# esp32B-2A.net
KiCad netlist of a schematic drawn in EAGLE
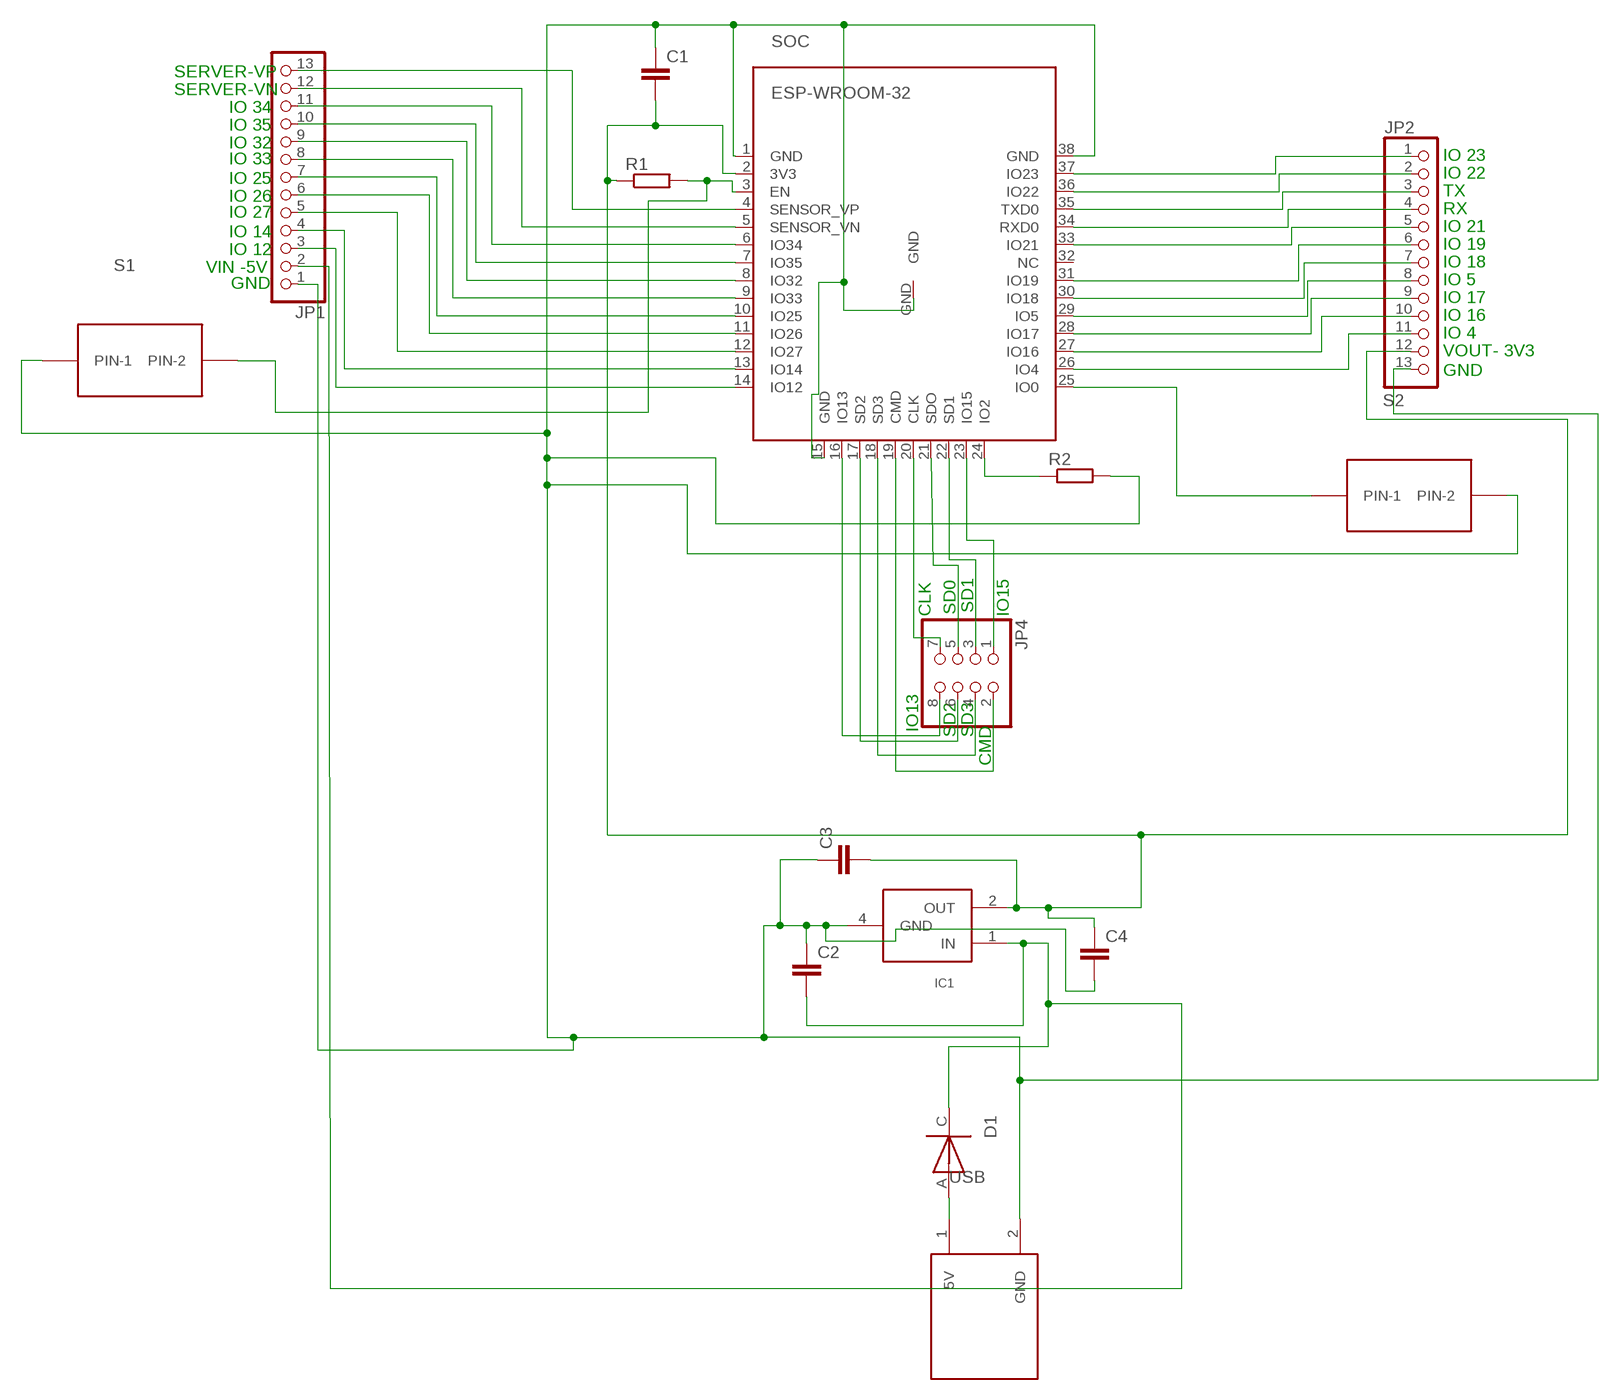
[diagram p0: schematic, sheet 1]

(export (version "E")
  (design (tool "Eeschema 10.0.6"))
  (components
    (comp (ref "C1")
      (value "C-EUC0603")
      (footprint "eagle-import:C0603")
      (libsource (lib "eagle-import") (part "C-EUC0603"))
    )
    (comp (ref "C2")
      (value "C-EUC0603")
      (footprint "eagle-import:C0603")
      (libsource (lib "eagle-import") (part "C-EUC0603"))
    )
    (comp (ref "C3")
      (value "C-EUC1206")
      (footprint "eagle-import:C1206")
      (libsource (lib "eagle-import") (part "C-EUC1206"))
    )
    (comp (ref "C4")
      (value "C-EUC1206")
      (footprint "eagle-import:C1206")
      (libsource (lib "eagle-import") (part "C-EUC1206"))
    )
    (comp (ref "D1")
      (value "DIODE-EX")
      (footprint "eagle-import:SOD80C")
      (libsource (lib "eagle-import") (part "DIODE-EX"))
    )
    (comp (ref "IC1")
      (value "NJM2845DL1")
      (footprint "eagle-import:NJM2845DL1-PKG")
      (libsource (lib "eagle-import") (part "NJM2845DL1"))
    )
    (comp (ref "JP1")
      (value "PINHD-1X13")
      (footprint "eagle-import:1X13")
      (libsource (lib "eagle-import") (part "PINHD-1X13"))
    )
    (comp (ref "JP2")
      (value "PINHD-1X13")
      (footprint "eagle-import:1X13")
      (libsource (lib "eagle-import") (part "PINHD-1X13"))
    )
    (comp (ref "JP4")
      (value "PINHD-2X4")
      (footprint "eagle-import:2X04")
      (libsource (lib "eagle-import") (part "PINHD-2X4"))
    )
    (comp (ref "R1")
      (value "R-EU_R0603")
      (footprint "eagle-import:R0603")
      (libsource (lib "eagle-import") (part "R-EU_R0603"))
    )
    (comp (ref "R2")
      (value "R-EU_R0603")
      (footprint "eagle-import:R0603")
      (libsource (lib "eagle-import") (part "R-EU_R0603"))
    )
    (comp (ref "S1")
      (value "BTN2-EX")
      (footprint "eagle-import:B3F-10XX")
      (libsource (lib "eagle-import") (part "BTN2-EX"))
    )
    (comp (ref "S2")
      (value "BTN2-EX")
      (footprint "eagle-import:B3F-10XX")
      (libsource (lib "eagle-import") (part "BTN2-EX"))
    )
    (comp (ref "SOC")
      (value "ESP-WROOM-32")
      (footprint "eagle-import:ESP-WROOM-32")
      (libsource (lib "eagle-import") (part "ESP-WROOM-32"))
    )
    (comp (ref "USB")
      (value "USB-CUST-1")
      (footprint "eagle-import:USB-CUST-1-PKG")
      (libsource (lib "eagle-import") (part "USB-CUST-1"))
    )
  )
  (nets
    (net (code "1") (name "Net-(IC1-GND)") (class "Default")
      (node (ref "C1") (pin "1") (pinfunction "1_1") (pintype "passive"))
      (node (ref "C2") (pin "1") (pinfunction "1_1") (pintype "passive"))
      (node (ref "C3") (pin "1") (pinfunction "1_1") (pintype "passive"))
      (node (ref "C4") (pin "2") (pinfunction "2_2") (pintype "passive"))
      (node (ref "IC1") (pin "4") (pinfunction "GND_4") (pintype "bidirectional"))
      (node (ref "JP1") (pin "1") (pinfunction "1_1") (pintype "passive"))
      (node (ref "JP2") (pin "13") (pinfunction "13_13") (pintype "passive"))
      (node (ref "R2") (pin "2") (pinfunction "2_2") (pintype "passive"))
      (node (ref "S1") (pin "1") (pinfunction "PIN-1_1") (pintype "bidirectional"))
      (node (ref "S2") (pin "2") (pinfunction "PIN-2_2") (pintype "bidirectional"))
      (node (ref "SOC") (pin "1") (pinfunction "GND_1") (pintype "bidirectional"))
      (node (ref "SOC") (pin "15") (pinfunction "GND_15") (pintype "bidirectional"))
      (node (ref "SOC") (pin "38") (pinfunction "GND_38") (pintype "bidirectional"))
      (node (ref "SOC") (pin "GND") (pinfunction "GND_GND") (pintype "bidirectional"))
      (node (ref "USB") (pin "2") (pinfunction "GND_2") (pintype "bidirectional"))
    )
    (net (code "2") (name "Net-(IC1-IN)") (class "Default")
      (node (ref "C2") (pin "2") (pinfunction "2_2") (pintype "passive"))
      (node (ref "D1") (pin "C") (pinfunction "C_C") (pintype "bidirectional"))
      (node (ref "IC1") (pin "1") (pinfunction "IN_1") (pintype "bidirectional"))
      (node (ref "JP1") (pin "2") (pinfunction "2_2") (pintype "passive"))
    )
    (net (code "3") (name "Net-(IC1-OUT)") (class "Default")
      (node (ref "C1") (pin "2") (pinfunction "2_2") (pintype "passive"))
      (node (ref "C3") (pin "2") (pinfunction "2_2") (pintype "passive"))
      (node (ref "C4") (pin "1") (pinfunction "1_1") (pintype "passive"))
      (node (ref "IC1") (pin "2") (pinfunction "OUT_2") (pintype "bidirectional"))
      (node (ref "JP2") (pin "12") (pinfunction "12_12") (pintype "passive"))
      (node (ref "R1") (pin "1") (pinfunction "1_1") (pintype "passive"))
      (node (ref "SOC") (pin "2") (pinfunction "3V3_2") (pintype "bidirectional"))
    )
    (net (code "4") (name "Net-(S1-PIN-2)") (class "Default")
      (node (ref "R1") (pin "2") (pinfunction "2_2") (pintype "passive"))
      (node (ref "S1") (pin "2") (pinfunction "PIN-2_2") (pintype "bidirectional"))
      (node (ref "SOC") (pin "3") (pinfunction "EN_3") (pintype "bidirectional"))
    )
    (net (code "5") (name "Net-(S2-PIN-1)") (class "Default")
      (node (ref "S2") (pin "1") (pinfunction "PIN-1_1") (pintype "bidirectional"))
      (node (ref "SOC") (pin "25") (pinfunction "IO0_25") (pintype "bidirectional"))
    )
    (net (code "6") (name "Net-(SOC-CLK)") (class "Default")
      (node (ref "JP4") (pin "7") (pinfunction "7_7") (pintype "passive"))
      (node (ref "SOC") (pin "20") (pinfunction "CLK_20") (pintype "bidirectional"))
    )
    (net (code "7") (name "Net-(SOC-CMD)") (class "Default")
      (node (ref "JP4") (pin "2") (pinfunction "2_2") (pintype "passive"))
      (node (ref "SOC") (pin "19") (pinfunction "CMD_19") (pintype "bidirectional"))
    )
    (net (code "8") (name "Net-(SOC-IO2)") (class "Default")
      (node (ref "R2") (pin "1") (pinfunction "1_1") (pintype "passive"))
      (node (ref "SOC") (pin "24") (pinfunction "IO2_24") (pintype "bidirectional"))
    )
    (net (code "9") (name "Net-(SOC-IO4)") (class "Default")
      (node (ref "JP2") (pin "11") (pinfunction "11_11") (pintype "passive"))
      (node (ref "SOC") (pin "26") (pinfunction "IO4_26") (pintype "bidirectional"))
    )
    (net (code "10") (name "Net-(SOC-IO5)") (class "Default")
      (node (ref "JP2") (pin "8") (pinfunction "8_8") (pintype "passive"))
      (node (ref "SOC") (pin "29") (pinfunction "IO5_29") (pintype "bidirectional"))
    )
    (net (code "11") (name "Net-(SOC-IO12)") (class "Default")
      (node (ref "JP1") (pin "3") (pinfunction "3_3") (pintype "passive"))
      (node (ref "SOC") (pin "14") (pinfunction "IO12_14") (pintype "bidirectional"))
    )
    (net (code "12") (name "Net-(SOC-IO13)") (class "Default")
      (node (ref "JP4") (pin "8") (pinfunction "8_8") (pintype "passive"))
      (node (ref "SOC") (pin "16") (pinfunction "IO13_16") (pintype "bidirectional"))
    )
    (net (code "13") (name "Net-(SOC-IO14)") (class "Default")
      (node (ref "JP1") (pin "4") (pinfunction "4_4") (pintype "passive"))
      (node (ref "SOC") (pin "13") (pinfunction "IO14_13") (pintype "bidirectional"))
    )
    (net (code "14") (name "Net-(SOC-IO15)") (class "Default")
      (node (ref "JP4") (pin "1") (pinfunction "1_1") (pintype "passive"))
      (node (ref "SOC") (pin "23") (pinfunction "IO15_23") (pintype "bidirectional"))
    )
    (net (code "15") (name "Net-(SOC-IO16)") (class "Default")
      (node (ref "JP2") (pin "10") (pinfunction "10_10") (pintype "passive"))
      (node (ref "SOC") (pin "27") (pinfunction "IO16_27") (pintype "bidirectional"))
    )
    (net (code "16") (name "Net-(SOC-IO17)") (class "Default")
      (node (ref "JP2") (pin "9") (pinfunction "9_9") (pintype "passive"))
      (node (ref "SOC") (pin "28") (pinfunction "IO17_28") (pintype "bidirectional"))
    )
    (net (code "17") (name "Net-(SOC-IO18)") (class "Default")
      (node (ref "JP2") (pin "7") (pinfunction "7_7") (pintype "passive"))
      (node (ref "SOC") (pin "30") (pinfunction "IO18_30") (pintype "bidirectional"))
    )
    (net (code "18") (name "Net-(SOC-IO19)") (class "Default")
      (node (ref "JP2") (pin "6") (pinfunction "6_6") (pintype "passive"))
      (node (ref "SOC") (pin "31") (pinfunction "IO19_31") (pintype "bidirectional"))
    )
    (net (code "19") (name "Net-(SOC-IO21)") (class "Default")
      (node (ref "JP2") (pin "5") (pinfunction "5_5") (pintype "passive"))
      (node (ref "SOC") (pin "33") (pinfunction "IO21_33") (pintype "bidirectional"))
    )
    (net (code "20") (name "Net-(SOC-IO22)") (class "Default")
      (node (ref "JP2") (pin "2") (pinfunction "2_2") (pintype "passive"))
      (node (ref "SOC") (pin "36") (pinfunction "IO22_36") (pintype "bidirectional"))
    )
    (net (code "21") (name "Net-(SOC-IO23)") (class "Default")
      (node (ref "JP2") (pin "1") (pinfunction "1_1") (pintype "passive"))
      (node (ref "SOC") (pin "37") (pinfunction "IO23_37") (pintype "bidirectional"))
    )
    (net (code "22") (name "Net-(SOC-IO25)") (class "Default")
      (node (ref "JP1") (pin "7") (pinfunction "7_7") (pintype "passive"))
      (node (ref "SOC") (pin "10") (pinfunction "IO25_10") (pintype "bidirectional"))
    )
    (net (code "23") (name "Net-(SOC-IO26)") (class "Default")
      (node (ref "JP1") (pin "6") (pinfunction "6_6") (pintype "passive"))
      (node (ref "SOC") (pin "11") (pinfunction "IO26_11") (pintype "bidirectional"))
    )
    (net (code "24") (name "Net-(SOC-IO27)") (class "Default")
      (node (ref "JP1") (pin "5") (pinfunction "5_5") (pintype "passive"))
      (node (ref "SOC") (pin "12") (pinfunction "IO27_12") (pintype "bidirectional"))
    )
    (net (code "25") (name "Net-(SOC-IO32)") (class "Default")
      (node (ref "JP1") (pin "9") (pinfunction "9_9") (pintype "passive"))
      (node (ref "SOC") (pin "8") (pinfunction "IO32_8") (pintype "bidirectional"))
    )
    (net (code "26") (name "Net-(SOC-IO33)") (class "Default")
      (node (ref "JP1") (pin "8") (pinfunction "8_8") (pintype "passive"))
      (node (ref "SOC") (pin "9") (pinfunction "IO33_9") (pintype "bidirectional"))
    )
    (net (code "27") (name "Net-(SOC-IO34)") (class "Default")
      (node (ref "JP1") (pin "11") (pinfunction "11_11") (pintype "passive"))
      (node (ref "SOC") (pin "6") (pinfunction "IO34_6") (pintype "bidirectional"))
    )
    (net (code "28") (name "Net-(SOC-IO35)") (class "Default")
      (node (ref "JP1") (pin "10") (pinfunction "10_10") (pintype "passive"))
      (node (ref "SOC") (pin "7") (pinfunction "IO35_7") (pintype "bidirectional"))
    )
    (net (code "29") (name "Net-(SOC-RXD0)") (class "Default")
      (node (ref "JP2") (pin "4") (pinfunction "4_4") (pintype "passive"))
      (node (ref "SOC") (pin "34") (pinfunction "RXD0_34") (pintype "bidirectional"))
    )
    (net (code "30") (name "Net-(SOC-SD1)") (class "Default")
      (node (ref "JP4") (pin "3") (pinfunction "3_3") (pintype "passive"))
      (node (ref "SOC") (pin "22") (pinfunction "SD1_22") (pintype "bidirectional"))
    )
    (net (code "31") (name "Net-(SOC-SD2)") (class "Default")
      (node (ref "JP4") (pin "6") (pinfunction "6_6") (pintype "passive"))
      (node (ref "SOC") (pin "17") (pinfunction "SD2_17") (pintype "bidirectional"))
    )
    (net (code "32") (name "Net-(SOC-SD3)") (class "Default")
      (node (ref "JP4") (pin "4") (pinfunction "4_4") (pintype "passive"))
      (node (ref "SOC") (pin "18") (pinfunction "SD3_18") (pintype "bidirectional"))
    )
    (net (code "33") (name "Net-(SOC-SDO)") (class "Default")
      (node (ref "JP4") (pin "5") (pinfunction "5_5") (pintype "passive"))
      (node (ref "SOC") (pin "21") (pinfunction "SDO_21") (pintype "bidirectional"))
    )
    (net (code "34") (name "Net-(SOC-SENSOR_VN)") (class "Default")
      (node (ref "JP1") (pin "12") (pinfunction "12_12") (pintype "passive"))
      (node (ref "SOC") (pin "5") (pinfunction "SENSOR_VN_5") (pintype "bidirectional"))
    )
    (net (code "35") (name "Net-(SOC-SENSOR_VP)") (class "Default")
      (node (ref "JP1") (pin "13") (pinfunction "13_13") (pintype "passive"))
      (node (ref "SOC") (pin "4") (pinfunction "SENSOR_VP_4") (pintype "bidirectional"))
    )
    (net (code "36") (name "Net-(SOC-TXD0)") (class "Default")
      (node (ref "JP2") (pin "3") (pinfunction "3_3") (pintype "passive"))
      (node (ref "SOC") (pin "35") (pinfunction "TXD0_35") (pintype "bidirectional"))
    )
    (net (code "37") (name "Net-(USB-5V)") (class "Default")
      (node (ref "D1") (pin "A") (pinfunction "A_A") (pintype "bidirectional"))
      (node (ref "USB") (pin "1") (pinfunction "5V_1") (pintype "bidirectional"))
    )
    (net (code "38") (name "unconnected-(SOC-NC-Pad32)") (class "Default")
      (node (ref "SOC") (pin "32") (pinfunction "NC_32") (pintype "bidirectional"))
    )
  )
)
